# Adafruit_Sparkle_Motion_WLED_Friend.net
KiCad netlist of a schematic drawn in EAGLE
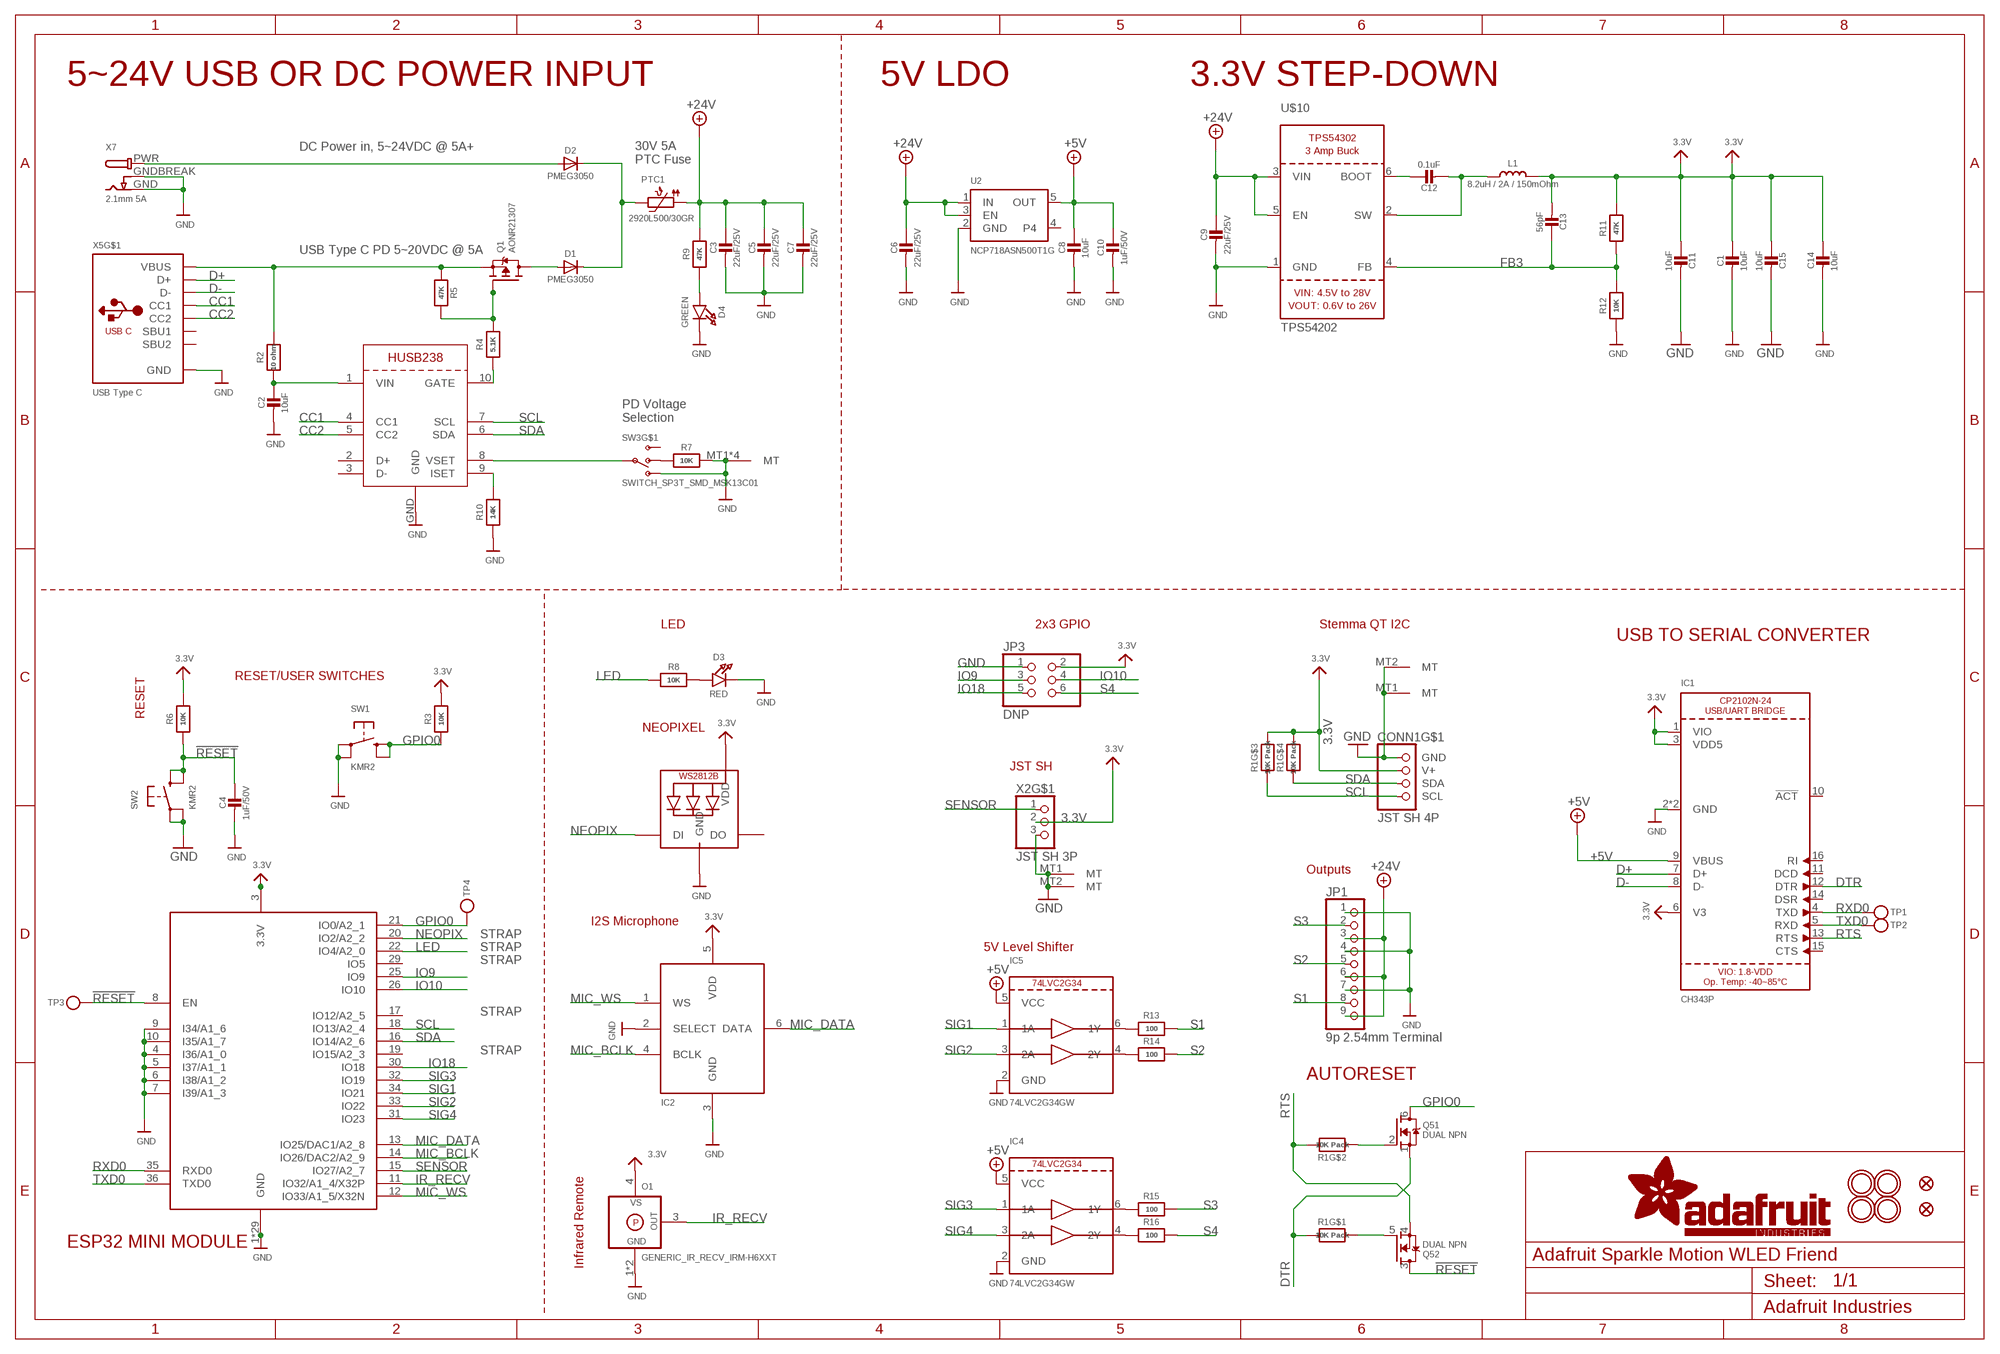
[diagram p0: schematic, sheet 1]

(export (version "E")
  (design (tool "Eeschema 10.0.6"))
  (components
    (comp (ref "C1")
      (value "10uF")
      (footprint "eagle-import:0805-NO")
      (libsource (lib "eagle-import") (part "CAP_CERAMIC0805-NOOUTLINE"))
    )
    (comp (ref "C2")
      (value "10uF")
      (footprint "eagle-import:0805-NO")
      (libsource (lib "eagle-import") (part "CAP_CERAMIC0805-NOOUTLINE"))
    )
    (comp (ref "C3")
      (value "22uF/25V")
      (footprint "eagle-import:0805-NO")
      (libsource (lib "eagle-import") (part "CAP_CERAMIC0805-NOOUTLINE"))
    )
    (comp (ref "C4")
      (value "1uF/50V")
      (footprint "eagle-import:0603-NO")
      (libsource (lib "eagle-import") (part "CAP_CERAMIC0603_NO"))
    )
    (comp (ref "C5")
      (value "22uF/25V")
      (footprint "eagle-import:0805-NO")
      (libsource (lib "eagle-import") (part "CAP_CERAMIC0805-NOOUTLINE"))
    )
    (comp (ref "C6")
      (value "22uF/25V")
      (footprint "eagle-import:0805-NO")
      (libsource (lib "eagle-import") (part "CAP_CERAMIC0805-NOOUTLINE"))
    )
    (comp (ref "C7")
      (value "22uF/25V")
      (footprint "eagle-import:0805-NO")
      (libsource (lib "eagle-import") (part "CAP_CERAMIC0805-NOOUTLINE"))
    )
    (comp (ref "C8")
      (value "10uF")
      (footprint "eagle-import:0805-NO")
      (fields (field (name "REV") "A"))
      (libsource (lib "eagle-import") (part "CAP_CERAMIC0805-NOOUTLINE"))
    )
    (comp (ref "C9")
      (value "22uF/25V")
      (footprint "eagle-import:0805-NO")
      (libsource (lib "eagle-import") (part "CAP_CERAMIC0805-NOOUTLINE"))
    )
    (comp (ref "C10")
      (value "1uF/50V")
      (footprint "eagle-import:0603-NO")
      (libsource (lib "eagle-import") (part "CAP_CERAMIC0603_NO"))
    )
    (comp (ref "C11")
      (value "10uF")
      (footprint "eagle-import:0805-NO")
      (libsource (lib "eagle-import") (part "CAP_CERAMIC0805-NOOUTLINE"))
    )
    (comp (ref "C12")
      (value "0.1uF")
      (footprint "eagle-import:0603-NO")
      (libsource (lib "eagle-import") (part "CAP_CERAMIC0603_NO"))
    )
    (comp (ref "C13")
      (value "56pF")
      (footprint "eagle-import:0603-NO")
      (libsource (lib "eagle-import") (part "CAP_CERAMIC0603_NO"))
    )
    (comp (ref "C14")
      (value "10uF")
      (footprint "eagle-import:0805-NO")
      (libsource (lib "eagle-import") (part "CAP_CERAMIC0805-NOOUTLINE"))
    )
    (comp (ref "C15")
      (value "10uF")
      (footprint "eagle-import:0805-NO")
      (libsource (lib "eagle-import") (part "CAP_CERAMIC0805-NOOUTLINE"))
    )
    (comp (ref "CONN1")
      (value "JST SH 4P")
      (footprint "eagle-import:JST_SH4")
      (libsource (lib "eagle-import") (part "STEMMA_I2C_QT"))
    )
    (comp (ref "D1")
      (value "PMEG3050")
      (footprint "eagle-import:SOD-128")
      (libsource (lib "eagle-import") (part "DIODE_SOD128"))
    )
    (comp (ref "D2")
      (value "PMEG3050")
      (footprint "eagle-import:SOD-128")
      (libsource (lib "eagle-import") (part "DIODE_SOD128"))
    )
    (comp (ref "D3")
      (value "RED")
      (footprint "eagle-import:CHIPLED_0603_NOOUTLINE")
      (libsource (lib "eagle-import") (part "LED0603_NOOUTLINE"))
    )
    (comp (ref "D4")
      (value "GREEN")
      (footprint "eagle-import:CHIPLED_0603_NOOUTLINE")
      (libsource (lib "eagle-import") (part "LED0603_NOOUTLINE"))
    )
    (comp (ref "IC1")
      (value "CH343P")
      (footprint "eagle-import:QFN16_3MM")
      (libsource (lib "eagle-import") (part "CH343P"))
    )
    (comp (ref "IC2")
      (value "ICS-43434")
      (footprint "eagle-import:SPH0645LM4H")
      (libsource (lib "eagle-import") (part "MIC_I2S_SPH0645"))
    )
    (comp (ref "IC4")
      (value "74LVC2G34GW")
      (footprint "eagle-import:SC70-6L")
      (libsource (lib "eagle-import") (part "74LVC2G34GW"))
    )
    (comp (ref "IC5")
      (value "74LVC2G34GW")
      (footprint "eagle-import:SC70-6L")
      (libsource (lib "eagle-import") (part "74LVC2G34GW"))
    )
    (comp (ref "JP1")
      (value "9p 2.54mm Terminal")
      (footprint "eagle-import:1X09_2.54MMTERMINAL")
      (libsource (lib "eagle-import") (part "HEADER-1X9_2.54MMTERM"))
    )
    (comp (ref "JP3")
      (value "DNP")
      (footprint "eagle-import:2X03_ROUND_70MIL")
      (libsource (lib "eagle-import") (part "HEADER-2X3"))
    )
    (comp (ref "L1")
      (value "8.2uH / 2A / 150mOhm")
      (footprint "eagle-import:INDUCTOR_5X5MM_NR5040_NOTHERMALS")
      (libsource (lib "eagle-import") (part "INDUCTORNR5040"))
    )
    (comp (ref "LED1")
      (value "WS2812B_SK6805_1515")
      (footprint "eagle-import:SK6805_1515")
      (libsource (lib "eagle-import") (part "WS2812B_SK6805_1515"))
    )
    (comp (ref "O1")
      (value "GENERIC_IR_RECV_IRM-H6XXT")
      (footprint "eagle-import:IRM-H6XXT")
      (libsource (lib "eagle-import") (part "GENERIC_IR_RECV_IRM-H6XXT"))
    )
    (comp (ref "PTC1")
      (value "2920L500/30GR")
      (footprint "eagle-import:PTC2920")
      (libsource (lib "eagle-import") (part "PTC_2920"))
    )
    (comp (ref "Q1")
      (value "AONR21307")
      (footprint "eagle-import:POWERDI3333")
      (libsource (lib "eagle-import") (part "MOSFET-P-POWERDI3333"))
    )
    (comp (ref "Q5")
      (value "DUAL NPN")
      (footprint "eagle-import:SOT363")
      (fields (field (name "JLC_ROTATION") "0"))
      (libsource (lib "eagle-import") (part "MOSFET-N_DUAL"))
    )
    (comp (ref "R1")
      (value "10K Pack")
      (footprint "eagle-import:RESPACK_4X0603")
      (libsource (lib "eagle-import") (part "RESISTOR_4PACK"))
    )
    (comp (ref "R2")
      (value "10 ohm")
      (footprint "eagle-import:0603-NO")
      (libsource (lib "eagle-import") (part "RESISTOR_0603_NOOUT"))
    )
    (comp (ref "R3")
      (value "10K")
      (footprint "eagle-import:0603-NO")
      (libsource (lib "eagle-import") (part "RESISTOR_0603_NOOUT"))
    )
    (comp (ref "R4")
      (value "5.1K")
      (footprint "eagle-import:0603-NO")
      (libsource (lib "eagle-import") (part "RESISTOR_0603_NOOUT"))
    )
    (comp (ref "R5")
      (value "47K")
      (footprint "eagle-import:0603-NO")
      (libsource (lib "eagle-import") (part "RESISTOR_0603_NOOUT"))
    )
    (comp (ref "R6")
      (value "10K")
      (footprint "eagle-import:0603-NO")
      (libsource (lib "eagle-import") (part "RESISTOR_0603_NOOUT"))
    )
    (comp (ref "R7")
      (value "10K")
      (footprint "eagle-import:0603-NO")
      (libsource (lib "eagle-import") (part "RESISTOR_0603_NOOUT"))
    )
    (comp (ref "R8")
      (value "10K")
      (footprint "eagle-import:0603-NO")
      (libsource (lib "eagle-import") (part "RESISTOR_0603_NOOUT"))
    )
    (comp (ref "R9")
      (value "47K")
      (footprint "eagle-import:0603-NO")
      (libsource (lib "eagle-import") (part "RESISTOR_0603_NOOUT"))
    )
    (comp (ref "R10")
      (value "14K")
      (footprint "eagle-import:0603-NO")
      (libsource (lib "eagle-import") (part "RESISTOR_0603_NOOUT"))
    )
    (comp (ref "R11")
      (value "47K")
      (footprint "eagle-import:0603-NO")
      (libsource (lib "eagle-import") (part "RESISTOR_0603_NOOUT"))
    )
    (comp (ref "R12")
      (value "10K")
      (footprint "eagle-import:0603-NO")
      (libsource (lib "eagle-import") (part "RESISTOR_0603_NOOUT"))
    )
    (comp (ref "R13")
      (value "100")
      (footprint "eagle-import:0603-NO")
      (libsource (lib "eagle-import") (part "RESISTOR_0603_NOOUT"))
    )
    (comp (ref "R14")
      (value "100")
      (footprint "eagle-import:0603-NO")
      (libsource (lib "eagle-import") (part "RESISTOR_0603_NOOUT"))
    )
    (comp (ref "R15")
      (value "100")
      (footprint "eagle-import:0603-NO")
      (libsource (lib "eagle-import") (part "RESISTOR_0603_NOOUT"))
    )
    (comp (ref "R16")
      (value "100")
      (footprint "eagle-import:0603-NO")
      (libsource (lib "eagle-import") (part "RESISTOR_0603_NOOUT"))
    )
    (comp (ref "SW1")
      (value "KMR2")
      (footprint "eagle-import:BTN_RKB2_4.6X2.8")
      (libsource (lib "eagle-import") (part "SWITCH_TACT_SMT_RKB2"))
    )
    (comp (ref "SW2")
      (value "KMR2")
      (footprint "eagle-import:BTN_RKB2_4.6X2.8")
      (libsource (lib "eagle-import") (part "SWITCH_TACT_SMT_RKB2"))
    )
    (comp (ref "SW3")
      (value "SWITCH_SP3T_SMD_MSK13C01")
      (footprint "eagle-import:MSK-13C01")
      (libsource (lib "eagle-import") (part "SWITCH_SP3T_SMD_MSK13C01"))
    )
    (comp (ref "TP1")
      (value "TESTPOINTROUND1.5MM")
      (footprint "eagle-import:TESTPOINT_ROUND_1.5MM")
      (libsource (lib "eagle-import") (part "TESTPOINTROUND1.5MM"))
    )
    (comp (ref "TP2")
      (value "TESTPOINTROUND1.5MM")
      (footprint "eagle-import:TESTPOINT_ROUND_1.5MM")
      (libsource (lib "eagle-import") (part "TESTPOINTROUND1.5MM"))
    )
    (comp (ref "TP3")
      (value "TESTPOINTROUND1.5MM")
      (footprint "eagle-import:TESTPOINT_ROUND_1.5MM")
      (libsource (lib "eagle-import") (part "TESTPOINTROUND1.5MM"))
    )
    (comp (ref "TP4")
      (value "TESTPOINTROUND1.5MM")
      (footprint "eagle-import:TESTPOINT_ROUND_1.5MM")
      (libsource (lib "eagle-import") (part "TESTPOINTROUND1.5MM"))
    )
    (comp (ref "U$10")
      (value "TPS54202")
      (footprint "eagle-import:SOT23-6")
      (libsource (lib "eagle-import") (part "TPS54302"))
    )
    (comp (ref "U$14")
      (value "MOUNTINGHOLE2.5")
      (footprint "eagle-import:MOUNTINGHOLE_2.5_PLATED")
      (libsource (lib "eagle-import") (part "MOUNTINGHOLE2.5"))
    )
    (comp (ref "U$20")
      (value "MOUNTINGHOLE2.5")
      (footprint "eagle-import:MOUNTINGHOLE_2.5_PLATED")
      (libsource (lib "eagle-import") (part "MOUNTINGHOLE2.5"))
    )
    (comp (ref "U$28")
      (value "MOUNTINGHOLE2.5")
      (footprint "eagle-import:MOUNTINGHOLE_2.5_PLATED")
      (libsource (lib "eagle-import") (part "MOUNTINGHOLE2.5"))
    )
    (comp (ref "U$31")
      (value "MOUNTINGHOLE2.5")
      (footprint "eagle-import:MOUNTINGHOLE_2.5_PLATED")
      (libsource (lib "eagle-import") (part "MOUNTINGHOLE2.5"))
    )
    (comp (ref "U$34")
      (value "FIDUCIAL_1MM")
      (footprint "eagle-import:FIDUCIAL_1MM")
      (libsource (lib "eagle-import") (part "FIDUCIAL_1MM"))
    )
    (comp (ref "U$35")
      (value "FIDUCIAL_1MM")
      (footprint "eagle-import:FIDUCIAL_1MM")
      (libsource (lib "eagle-import") (part "FIDUCIAL_1MM"))
    )
    (comp (ref "U2")
      (value "NCP718ASN500T1G")
      (footprint "eagle-import:SOT23-5")
      (fields (field (name "JLC_ROTATION") "0"))
      (libsource (lib "eagle-import") (part "VREG_SOT23-5"))
    )
    (comp (ref "X2")
      (value "JST SH 3P")
      (footprint "eagle-import:JST_SH3")
      (libsource (lib "eagle-import") (part "CON_JST_SH_3PINHORZ"))
    )
    (comp (ref "X3")
      (value "HUSB238")
      (footprint "eagle-import:DFN10_3X3MM")
      (libsource (lib "eagle-import") (part "HUSB238"))
    )
    (comp (ref "X4")
      (value "ESP32-MINI-1")
      (footprint "eagle-import:ESP32-MINI-1")
      (libsource (lib "eagle-import") (part "ESP32-MINI-1"))
    )
    (comp (ref "X5")
      (value "USB Type C")
      (footprint "eagle-import:USB_C_CUSB31-CFM2AX-01-X")
      (libsource (lib "eagle-import") (part "USB_C"))
    )
    (comp (ref "X7")
      (value "2.1mm 5A")
      (footprint "eagle-import:DCJACK_2MM_PTH")
      (libsource (lib "eagle-import") (part "DCBARRELPTH"))
    )
  )
  (nets
    (net (code "1") (name "+5V") (class "Default")
      (node (ref "C10") (pin "1") (pinfunction "1_1") (pintype "passive"))
      (node (ref "C8") (pin "1") (pinfunction "1_1") (pintype "passive"))
      (node (ref "IC1") (pin "9") (pinfunction "VBUS_9") (pintype "power_in"))
      (node (ref "IC4") (pin "5") (pinfunction "VCC_5") (pintype "power_in"))
      (node (ref "IC5") (pin "5") (pinfunction "VCC_5") (pintype "power_in"))
      (node (ref "U2") (pin "5") (pinfunction "OUT_5") (pintype "power_in"))
    )
    (net (code "2") (name "+24V") (class "Default")
      (node (ref "C3") (pin "1") (pinfunction "1_1") (pintype "passive"))
      (node (ref "C5") (pin "1") (pinfunction "1_1") (pintype "passive"))
      (node (ref "C6") (pin "1") (pinfunction "1_1") (pintype "passive"))
      (node (ref "C7") (pin "1") (pinfunction "1_1") (pintype "passive"))
      (node (ref "C9") (pin "1") (pinfunction "1_1") (pintype "passive"))
      (node (ref "JP1") (pin "3") (pinfunction "3_3") (pintype "passive"))
      (node (ref "JP1") (pin "6") (pinfunction "6_6") (pintype "passive"))
      (node (ref "JP1") (pin "9") (pinfunction "9_9") (pintype "passive"))
      (node (ref "PTC1") (pin "P$1") (pinfunction "1_P$1") (pintype "passive"))
      (node (ref "R9") (pin "2") (pinfunction "2_2") (pintype "passive"))
      (node (ref "U$10") (pin "3") (pinfunction "VIN_3") (pintype "power_in"))
      (node (ref "U$10") (pin "5") (pinfunction "EN_5") (pintype "input"))
      (node (ref "U2") (pin "1") (pinfunction "IN_1") (pintype "power_in"))
      (node (ref "U2") (pin "3") (pinfunction "EN_3") (pintype "input"))
    )
    (net (code "3") (name "/CC1") (class "Default")
      (node (ref "X3") (pin "4") (pinfunction "CC1_4") (pintype "input"))
      (node (ref "X5") (pin "A5") (pinfunction "CC1_A5") (pintype "bidirectional"))
    )
    (net (code "4") (name "/CC2") (class "Default")
      (node (ref "X3") (pin "5") (pinfunction "CC2_5") (pintype "input"))
      (node (ref "X5") (pin "B5") (pinfunction "CC2_B5") (pintype "bidirectional"))
    )
    (net (code "5") (name "/D+") (class "Default")
      (node (ref "IC1") (pin "7") (pinfunction "D+_7") (pintype "bidirectional"))
      (node (ref "X5") (pin "A6") (pinfunction "D+_A6") (pintype "bidirectional"))
      (node (ref "X5") (pin "B6") (pinfunction "D+_B6") (pintype "bidirectional"))
    )
    (net (code "6") (name "/D-") (class "Default")
      (node (ref "IC1") (pin "8") (pinfunction "D-_8") (pintype "bidirectional"))
      (node (ref "X5") (pin "A7") (pinfunction "D-_A7") (pintype "bidirectional"))
      (node (ref "X5") (pin "B7") (pinfunction "D-_B7") (pintype "bidirectional"))
    )
    (net (code "7") (name "/DTR") (class "Default")
      (node (ref "IC1") (pin "12") (pinfunction "DTR_12") (pintype "output"))
      (node (ref "Q5") (pin "1") (pinfunction "S_1") (pintype "bidirectional"))
      (node (ref "R1") (pin "1") (pinfunction "1_1") (pintype "passive"))
    )
    (net (code "8") (name "/FB3") (class "Default")
      (node (ref "C13") (pin "1") (pinfunction "1_1") (pintype "passive"))
      (node (ref "R11") (pin "1") (pinfunction "1_1") (pintype "passive"))
      (node (ref "R12") (pin "2") (pinfunction "2_2") (pintype "passive"))
      (node (ref "U$10") (pin "4") (pinfunction "FB_4") (pintype "input"))
    )
    (net (code "9") (name "/GPIO0") (class "Default")
      (node (ref "Q5") (pin "6") (pinfunction "D_6") (pintype "bidirectional"))
      (node (ref "R3") (pin "1") (pinfunction "1_1") (pintype "passive"))
      (node (ref "SW1") (pin "B") (pinfunction "S_B") (pintype "passive"))
      (node (ref "SW1") (pin "B'") (pinfunction "S1_B'") (pintype "passive"))
      (node (ref "TP4") (pin "P$1") (pinfunction "P$1_P$1") (pintype "bidirectional"))
      (node (ref "X4") (pin "21") (pinfunction "IO0/A2_1_21") (pintype "bidirectional"))
    )
    (net (code "10") (name "/IO9") (class "Default")
      (node (ref "JP3") (pin "3") (pinfunction "3_3") (pintype "passive"))
      (node (ref "X4") (pin "25") (pinfunction "IO9_25") (pintype "bidirectional"))
    )
    (net (code "11") (name "/IO10") (class "Default")
      (node (ref "JP3") (pin "4") (pinfunction "4_4") (pintype "passive"))
      (node (ref "X4") (pin "26") (pinfunction "IO10_26") (pintype "bidirectional"))
    )
    (net (code "12") (name "/IO18") (class "Default")
      (node (ref "JP3") (pin "5") (pinfunction "5_5") (pintype "passive"))
      (node (ref "X4") (pin "30") (pinfunction "IO18_30") (pintype "bidirectional"))
    )
    (net (code "13") (name "/IR_RECV") (class "Default")
      (node (ref "O1") (pin "3") (pinfunction "OUT_3") (pintype "output"))
      (node (ref "X4") (pin "11") (pinfunction "IO32/A1_4/X32P_11") (pintype "bidirectional"))
    )
    (net (code "14") (name "/LED") (class "Default")
      (node (ref "R8") (pin "1") (pinfunction "1_1") (pintype "passive"))
      (node (ref "X4") (pin "22") (pinfunction "IO4/A2_0_22") (pintype "bidirectional"))
    )
    (net (code "15") (name "/MIC_BCLK") (class "Default")
      (node (ref "IC2") (pin "4") (pinfunction "BCLK_4") (pintype "input"))
      (node (ref "X4") (pin "14") (pinfunction "IO26/DAC2/A2_9_14") (pintype "bidirectional"))
    )
    (net (code "16") (name "/MIC_DATA") (class "Default")
      (node (ref "IC2") (pin "6") (pinfunction "DATA_6") (pintype "output"))
      (node (ref "X4") (pin "13") (pinfunction "IO25/DAC1/A2_8_13") (pintype "bidirectional"))
    )
    (net (code "17") (name "/MIC_WS") (class "Default")
      (node (ref "IC2") (pin "1") (pinfunction "WS_1") (pintype "input"))
      (node (ref "X4") (pin "12") (pinfunction "IO33/A1_5/X32N_12") (pintype "bidirectional"))
    )
    (net (code "18") (name "/NEOPIX") (class "Default")
      (node (ref "LED1") (pin "1") (pinfunction "DI_1") (pintype "input"))
      (node (ref "X4") (pin "20") (pinfunction "IO2/A2_2_20") (pintype "bidirectional"))
    )
    (net (code "19") (name "/RTS") (class "Default")
      (node (ref "IC1") (pin "13") (pinfunction "RTS_13") (pintype "output"))
      (node (ref "Q5") (pin "4") (pinfunction "S_4") (pintype "bidirectional"))
      (node (ref "R1") (pin "7") (pinfunction "2_7") (pintype "passive"))
    )
    (net (code "20") (name "/RXD0") (class "Default")
      (node (ref "IC1") (pin "4") (pinfunction "TXD_4") (pintype "output"))
      (node (ref "TP1") (pin "P$1") (pinfunction "P$1_P$1") (pintype "bidirectional"))
      (node (ref "X4") (pin "35") (pinfunction "RXD0_35") (pintype "input"))
    )
    (net (code "21") (name "/S1") (class "Default")
      (node (ref "JP1") (pin "8") (pinfunction "8_8") (pintype "passive"))
      (node (ref "R13") (pin "2") (pinfunction "2_2") (pintype "passive"))
    )
    (net (code "22") (name "/S2") (class "Default")
      (node (ref "JP1") (pin "5") (pinfunction "5_5") (pintype "passive"))
      (node (ref "R14") (pin "2") (pinfunction "2_2") (pintype "passive"))
    )
    (net (code "23") (name "/S3") (class "Default")
      (node (ref "JP1") (pin "2") (pinfunction "2_2") (pintype "passive"))
      (node (ref "R15") (pin "2") (pinfunction "2_2") (pintype "passive"))
    )
    (net (code "24") (name "/S4") (class "Default")
      (node (ref "JP3") (pin "6") (pinfunction "6_6") (pintype "passive"))
      (node (ref "R16") (pin "2") (pinfunction "2_2") (pintype "passive"))
    )
    (net (code "25") (name "/SCL") (class "Default")
      (node (ref "CONN1") (pin "4") (pinfunction "SCL_4") (pintype "passive"))
      (node (ref "R1") (pin "3") (pinfunction "1_3") (pintype "passive"))
      (node (ref "X3") (pin "7") (pinfunction "SCL_7") (pintype "bidirectional"))
      (node (ref "X4") (pin "18") (pinfunction "IO13/A2_4_18") (pintype "bidirectional"))
    )
    (net (code "26") (name "/SDA") (class "Default")
      (node (ref "CONN1") (pin "3") (pinfunction "SDA_3") (pintype "passive"))
      (node (ref "R1") (pin "4") (pinfunction "1_4") (pintype "passive"))
      (node (ref "X3") (pin "6") (pinfunction "SDA_6") (pintype "bidirectional"))
      (node (ref "X4") (pin "16") (pinfunction "IO14/A2_6_16") (pintype "bidirectional"))
    )
    (net (code "27") (name "/SENSOR") (class "Default")
      (node (ref "X2") (pin "1") (pinfunction "1_1") (pintype "passive"))
      (node (ref "X4") (pin "15") (pinfunction "IO27/A2_7_15") (pintype "bidirectional"))
    )
    (net (code "28") (name "/SIG1") (class "Default")
      (node (ref "IC5") (pin "1") (pinfunction "1A_1") (pintype "input"))
      (node (ref "X4") (pin "34") (pinfunction "IO21_34") (pintype "bidirectional"))
    )
    (net (code "29") (name "/SIG2") (class "Default")
      (node (ref "IC5") (pin "3") (pinfunction "2A_3") (pintype "input"))
      (node (ref "X4") (pin "33") (pinfunction "IO22_33") (pintype "bidirectional"))
    )
    (net (code "30") (name "/SIG3") (class "Default")
      (node (ref "IC4") (pin "1") (pinfunction "1A_1") (pintype "input"))
      (node (ref "X4") (pin "32") (pinfunction "IO19_32") (pintype "bidirectional"))
    )
    (net (code "31") (name "/SIG4") (class "Default")
      (node (ref "IC4") (pin "3") (pinfunction "2A_3") (pintype "input"))
      (node (ref "X4") (pin "31") (pinfunction "IO23_31") (pintype "bidirectional"))
    )
    (net (code "32") (name "/TXD0") (class "Default")
      (node (ref "IC1") (pin "5") (pinfunction "RXD_5") (pintype "input"))
      (node (ref "TP2") (pin "P$1") (pinfunction "P$1_P$1") (pintype "bidirectional"))
      (node (ref "X4") (pin "36") (pinfunction "TXD0_36") (pintype "output"))
    )
    (net (code "33") (name "/~{RESET}") (class "Default")
      (node (ref "C4") (pin "1") (pinfunction "1_1") (pintype "passive"))
      (node (ref "Q5") (pin "3") (pinfunction "D_3") (pintype "bidirectional"))
      (node (ref "R6") (pin "1") (pinfunction "1_1") (pintype "passive"))
      (node (ref "SW2") (pin "B") (pinfunction "S_B") (pintype "passive"))
      (node (ref "SW2") (pin "B'") (pinfunction "S1_B'") (pintype "passive"))
      (node (ref "TP3") (pin "P$1") (pinfunction "P$1_P$1") (pintype "bidirectional"))
      (node (ref "X4") (pin "8") (pinfunction "EN_8") (pintype "input"))
    )
    (net (code "34") (name "3.3V") (class "Default")
      (node (ref "C1") (pin "1") (pinfunction "1_1") (pintype "passive"))
      (node (ref "C11") (pin "1") (pinfunction "1_1") (pintype "passive"))
      (node (ref "C13") (pin "2") (pinfunction "2_2") (pintype "passive"))
      (node (ref "C14") (pin "1") (pinfunction "1_1") (pintype "passive"))
      (node (ref "C15") (pin "1") (pinfunction "1_1") (pintype "passive"))
      (node (ref "CONN1") (pin "2") (pinfunction "V+_2") (pintype "passive"))
      (node (ref "IC1") (pin "1") (pinfunction "VIO_1") (pintype "power_in"))
      (node (ref "IC1") (pin "3") (pinfunction "VDD5_3") (pintype "power_in"))
      (node (ref "IC1") (pin "6") (pinfunction "V3_6") (pintype "passive"))
      (node (ref "IC2") (pin "5") (pinfunction "VDD_5") (pintype "power_in"))
      (node (ref "JP3") (pin "2") (pinfunction "2_2") (pintype "passive"))
      (node (ref "L1") (pin "P$2") (pinfunction "2_P$2") (pintype "passive"))
      (node (ref "LED1") (pin "2") (pinfunction "VDD_2") (pintype "power_in"))
      (node (ref "O1") (pin "4") (pinfunction "VS_4") (pintype "power_in"))
      (node (ref "R1") (pin "5") (pinfunction "2_5") (pintype "passive"))
      (node (ref "R1") (pin "6") (pinfunction "2_6") (pintype "passive"))
      (node (ref "R11") (pin "2") (pinfunction "2_2") (pintype "passive"))
      (node (ref "R3") (pin "2") (pinfunction "2_2") (pintype "passive"))
      (node (ref "R6") (pin "2") (pinfunction "2_2") (pintype "passive"))
      (node (ref "X2") (pin "2") (pinfunction "2_2") (pintype "passive"))
      (node (ref "X4") (pin "3") (pinfunction "3.3V_3") (pintype "passive"))
    )
    (net (code "35") (name "GND") (class "Default")
      (node (ref "C1") (pin "2") (pinfunction "2_2") (pintype "passive"))
      (node (ref "C10") (pin "2") (pinfunction "2_2") (pintype "passive"))
      (node (ref "C11") (pin "2") (pinfunction "2_2") (pintype "passive"))
      (node (ref "C14") (pin "2") (pinfunction "2_2") (pintype "passive"))
      (node (ref "C15") (pin "2") (pinfunction "2_2") (pintype "passive"))
      (node (ref "C2") (pin "2") (pinfunction "2_2") (pintype "passive"))
      (node (ref "C3") (pin "2") (pinfunction "2_2") (pintype "passive"))
      (node (ref "C4") (pin "2") (pinfunction "2_2") (pintype "passive"))
      (node (ref "C5") (pin "2") (pinfunction "2_2") (pintype "passive"))
      (node (ref "C6") (pin "2") (pinfunction "2_2") (pintype "passive"))
      (node (ref "C7") (pin "2") (pinfunction "2_2") (pintype "passive"))
      (node (ref "C8") (pin "2") (pinfunction "2_2") (pintype "passive"))
      (node (ref "C9") (pin "2") (pinfunction "2_2") (pintype "passive"))
      (node (ref "CONN1") (pin "1") (pinfunction "GND_1") (pintype "passive"))
      (node (ref "CONN1") (pin "MT1") (pinfunction "MT_MT1") (pintype "bidirectional"))
      (node (ref "CONN1") (pin "MT2") (pinfunction "MT_MT2") (pintype "bidirectional"))
      (node (ref "D3") (pin "C") (pinfunction "C_C") (pintype "passive"))
      (node (ref "D4") (pin "C") (pinfunction "C_C") (pintype "passive"))
      (node (ref "IC1") (pin "2") (pinfunction "GND_2") (pintype "power_in"))
      (node (ref "IC1") (pin "THERMAL") (pinfunction "GND_THERMAL") (pintype "power_in"))
      (node (ref "IC2") (pin "2") (pinfunction "SELECT_2") (pintype "input"))
      (node (ref "IC2") (pin "3") (pinfunction "GND_3") (pintype "power_in"))
      (node (ref "IC4") (pin "2") (pinfunction "GND_2") (pintype "power_in"))
      (node (ref "IC5") (pin "2") (pinfunction "GND_2") (pintype "power_in"))
      (node (ref "JP1") (pin "1") (pinfunction "1_1") (pintype "passive"))
      (node (ref "JP1") (pin "4") (pinfunction "4_4") (pintype "passive"))
      (node (ref "JP1") (pin "7") (pinfunction "7_7") (pintype "passive"))
      (node (ref "JP3") (pin "1") (pinfunction "1_1") (pintype "passive"))
      (node (ref "LED1") (pin "4") (pinfunction "GND_4") (pintype "power_in"))
      (node (ref "O1") (pin "1") (pinfunction "GND_1") (pintype "power_in"))
      (node (ref "O1") (pin "2") (pinfunction "GND_2") (pintype "power_in"))
      (node (ref "R10") (pin "1") (pinfunction "1_1") (pintype "passive"))
      (node (ref "R12") (pin "1") (pinfunction "1_1") (pintype "passive"))
      (node (ref "R7") (pin "1") (pinfunction "1_1") (pintype "passive"))
      (node (ref "SW1") (pin "A") (pinfunction "P_A") (pintype "passive"))
      (node (ref "SW1") (pin "A'") (pinfunction "P1_A'") (pintype "passive"))
      (node (ref "SW2") (pin "A") (pinfunction "P_A") (pintype "passive"))
      (node (ref "SW2") (pin "A'") (pinfunction "P1_A'") (pintype "passive"))
      (node (ref "SW3") (pin "4") (pinfunction "3_4") (pintype "passive"))
      (node (ref "SW3") (pin "MT1") (pinfunction "MT_MT1") (pintype "bidirectional"))
      (node (ref "SW3") (pin "MT2") (pinfunction "MT_MT2") (pintype "bidirectional"))
      (node (ref "SW3") (pin "MT3") (pinfunction "MT_MT3") (pintype "bidirectional"))
      (node (ref "SW3") (pin "MT4") (pinfunction "MT_MT4") (pintype "bidirectional"))
      (node (ref "U$10") (pin "1") (pinfunction "GND_1") (pintype "power_in"))
      (node (ref "U2") (pin "2") (pinfunction "GND_2") (pintype "power_in"))
      (node (ref "X2") (pin "3") (pinfunction "3_3") (pintype "passive"))
      (node (ref "X2") (pin "MT1") (pinfunction "MT_MT1") (pintype "bidirectional"))
      (node (ref "X2") (pin "MT2") (pinfunction "MT_MT2") (pintype "bidirectional"))
      (node (ref "X3") (pin "GND") (pinfunction "GND_GND") (pintype "power_in"))
      (node (ref "X4") (pin "1") (pinfunction "GND_1") (pintype "passive"))
      (node (ref "X4") (pin "10") (pinfunction "I35/A1_7_10") (pintype "input"))
      (node (ref "X4") (pin "2") (pinfunction "GND_2") (pintype "passive"))
      (node (ref "X4") (pin "27") (pinfunction "GND_27") (pintype "passive"))
      (node (ref "X4") (pin "38") (pinfunction "GND_38") (pintype "passive"))
      (node (ref "X4") (pin "39") (pinfunction "GND_39") (pintype "passive"))
      (node (ref "X4") (pin "4") (pinfunction "I36/A1_0_4") (pintype "input"))
      (node (ref "X4") (pin "40") (pinfunction "GND_40") (pintype "passive"))
      (node (ref "X4") (pin "41") (pinfunction "GND_41") (pintype "passive"))
      (node (ref "X4") (pin "42") (pinfunction "GND_42") (pintype "passive"))
      (node (ref "X4") (pin "43") (pinfunction "GND_43") (pintype "passive"))
      (node (ref "X4") (pin "44") (pinfunction "GND_44") (pintype "passive"))
      (node (ref "X4") (pin "45") (pinfunction "GND_45") (pintype "passive"))
      (node (ref "X4") (pin "46") (pinfunction "GND_46") (pintype "passive"))
      (node (ref "X4") (pin "47") (pinfunction "GND_47") (pintype "passive"))
      (node (ref "X4") (pin "48") (pinfunction "GND_48") (pintype "passive"))
      (node (ref "X4") (pin "49") (pinfunction "GND_49") (pintype "passive"))
      (node (ref "X4") (pin "5") (pinfunction "I37/A1_1_5") (pintype "input"))
      (node (ref "X4") (pin "50") (pinfunction "GND_50") (pintype "passive"))
      (node (ref "X4") (pin "51") (pinfunction "GND_51") (pintype "passive"))
      (node (ref "X4") (pin "52") (pinfunction "GND_52") (pintype "passive"))
      (node (ref "X4") (pin "53") (pinfunction "GND_53") (pintype "passive"))
      (node (ref "X4") (pin "54") (pinfunction "GND_54") (pintype "passive"))
      (node (ref "X4") (pin "55") (pinfunction "GND_55") (pintype "passive"))
      (node (ref "X4") (pin "56") (pinfunction "GND_56") (pintype "passive"))
      (node (ref "X4") (pin "57") (pinfunction "GND_57") (pintype "passive"))
      (node (ref "X4") (pin "58") (pinfunction "GND_58") (pintype "passive"))
      (node (ref "X4") (pin "59") (pinfunction "GND_59") (pintype "passive"))
      (node (ref "X4") (pin "6") (pinfunction "I38/A1_2_6") (pintype "input"))
      (node (ref "X4") (pin "60") (pinfunction "GND_60") (pintype "passive"))
      (node (ref "X4") (pin "61") (pinfunction "GND_61") (pintype "passive"))
      (node (ref "X4") (pin "62") (pinfunction "GND_62") (pintype "passive"))
      (node (ref "X4") (pin "63") (pinfunction "GND_63") (pintype "passive"))
      (node (ref "X4") (pin "7") (pinfunction "I39/A1_3_7") (pintype "input"))
      (node (ref "X4") (pin "9") (pinfunction "I34/A1_6_9") (pintype "input"))
      (node (ref "X5") (pin "A1B12") (pinfunction "GND_A1B12") (pintype "power_in"))
      (node (ref "X5") (pin "B1A12") (pinfunction "GND_B1A12") (pintype "power_in"))
      (node (ref "X7") (pin "GND") (pinfunction "GND_GND") (pintype "power_in"))
      (node (ref "X7") (pin "GNDBREAK") (pinfunction "GNDBREAK_GNDBREAK") (pintype "power_in"))
    )
    (net (code "36") (name "Net-(D2-PadA)") (class "Default")
      (node (ref "D2") (pin "A") (pinfunction "A_A") (pintype "passive"))
      (node (ref "X7") (pin "PWR") (pinfunction "PWR_PWR") (pintype "power_in"))
    )
    (net (code "37") (name "Net-(D3-PadA)") (class "Default")
      (node (ref "D3") (pin "A") (pinfunction "A_A") (pintype "passive"))
      (node (ref "R8") (pin "2") (pinfunction "2_2") (pintype "passive"))
    )
    (net (code "38") (name "Net-(D4-PadA)") (class "Default")
      (node (ref "D4") (pin "A") (pinfunction "A_A") (pintype "passive"))
      (node (ref "R9") (pin "1") (pinfunction "1_1") (pintype "passive"))
    )
    (net (code "39") (name "Net-(IC4-1Y)") (class "Default")
      (node (ref "IC4") (pin "6") (pinfunction "1Y_6") (pintype "output"))
      (node (ref "R15") (pin "1") (pinfunction "1_1") (pintype "passive"))
    )
    (net (code "40") (name "Net-(IC4-2Y)") (class "Default")
      (node (ref "IC4") (pin "4") (pinfunction "2Y_4") (pintype "output"))
      (node (ref "R16") (pin "1") (pinfunction "1_1") (pintype "passive"))
    )
    (net (code "41") (name "Net-(IC5-1Y)") (class "Default")
      (node (ref "IC5") (pin "6") (pinfunction "1Y_6") (pintype "output"))
      (node (ref "R13") (pin "1") (pinfunction "1_1") (pintype "passive"))
    )
    (net (code "42") (name "Net-(IC5-2Y)") (class "Default")
      (node (ref "IC5") (pin "4") (pinfunction "2Y_4") (pintype "output"))
      (node (ref "R14") (pin "1") (pinfunction "1_1") (pintype "passive"))
    )
    (net (code "43") (name "Net-(L1-1)") (class "Default")
      (node (ref "C12") (pin "2") (pinfunction "2_2") (pintype "passive"))
      (node (ref "L1") (pin "P$1") (pinfunction "1_P$1") (pintype "passive"))
      (node (ref "U$10") (pin "2") (pinfunction "SW_2") (pintype "power_in"))
    )
    (net (code "44") (name "Net-(PTC1-2)") (class "Default")
      (node (ref "D1") (pin "C") (pinfunction "C_C") (pintype "passive"))
      (node (ref "D2") (pin "C") (pinfunction "C_C") (pintype "passive"))
      (node (ref "PTC1") (pin "P$2") (pinfunction "2_P$2") (pintype "passive"))
    )
    (net (code "45") (name "Net-(Q1-D)") (class "Default")
      (node (ref "D1") (pin "A") (pinfunction "A_A") (pintype "passive"))
      (node (ref "Q1") (pin "5678") (pinfunction "D_5678") (pintype "passive"))
    )
    (net (code "46") (name "Net-(Q1-G)") (class "Default")
      (node (ref "Q1") (pin "4") (pinfunction "G_4") (pintype "passive"))
      (node (ref "R4") (pin "2") (pinfunction "2_2") (pintype "passive"))
      (node (ref "R5") (pin "2") (pinfunction "2_2") (pintype "passive"))
    )
    (net (code "47") (name "Net-(Q1-S-Pad1)") (class "Default")
      (node (ref "Q1") (pin "1") (pinfunction "S_1") (pintype "passive"))
      (node (ref "Q1") (pin "2") (pinfunction "S_2") (pintype "passive"))
      (node (ref "Q1") (pin "3") (pinfunction "S_3") (pintype "passive"))
      (node (ref "R2") (pin "2") (pinfunction "2_2") (pintype "passive"))
      (node (ref "R5") (pin "1") (pinfunction "1_1") (pintype "passive"))
      (node (ref "X5") (pin "A4B9") (pinfunction "VBUS_A4B9") (pintype "power_in"))
      (node (ref "X5") (pin "B4A9") (pinfunction "VBUS_B4A9") (pintype "power_in"))
    )
    (net (code "48") (name "Net-(Q5A-G)") (class "Default")
      (node (ref "Q5") (pin "2") (pinfunction "G_2") (pintype "bidirectional"))
      (node (ref "R1") (pin "2") (pinfunction "1_2") (pintype "passive"))
    )
    (net (code "49") (name "Net-(Q5B-G)") (class "Default")
      (node (ref "Q5") (pin "5") (pinfunction "G_5") (pintype "bidirectional"))
      (node (ref "R1") (pin "8") (pinfunction "2_8") (pintype "passive"))
    )
    (net (code "50") (name "Net-(R7-Pad2)") (class "Default")
      (node (ref "R7") (pin "2") (pinfunction "2_2") (pintype "passive"))
      (node (ref "SW3") (pin "2") (pinfunction "2_2") (pintype "passive"))
    )
    (net (code "51") (name "Net-(SW3A-P)") (class "Default")
      (node (ref "SW3") (pin "3") (pinfunction "P_3") (pintype "passive"))
      (node (ref "X3") (pin "8") (pinfunction "VSET_8") (pintype "passive"))
    )
    (net (code "52") (name "Net-(U$10-BOOT)") (class "Default")
      (node (ref "C12") (pin "1") (pinfunction "1_1") (pintype "passive"))
      (node (ref "U$10") (pin "6") (pinfunction "BOOT_6") (pintype "passive"))
    )
    (net (code "53") (name "Net-(X3-GATE)") (class "Default")
      (node (ref "R4") (pin "1") (pinfunction "1_1") (pintype "passive"))
      (node (ref "X3") (pin "10") (pinfunction "GATE_10") (pintype "output"))
    )
    (net (code "54") (name "Net-(X3-ISET)") (class "Default")
      (node (ref "R10") (pin "2") (pinfunction "2_2") (pintype "passive"))
      (node (ref "X3") (pin "9") (pinfunction "ISET_9") (pintype "passive"))
    )
    (net (code "55") (name "Net-(X3-VIN)") (class "Default")
      (node (ref "C2") (pin "1") (pinfunction "1_1") (pintype "passive"))
      (node (ref "R2") (pin "1") (pinfunction "1_1") (pintype "passive"))
      (node (ref "X3") (pin "1") (pinfunction "VIN_1") (pintype "power_in"))
    )
    (net (code "56") (name "unconnected-(IC1-CTS-Pad15)") (class "Default")
      (node (ref "IC1") (pin "15") (pinfunction "CTS_15") (pintype "input"))
    )
    (net (code "57") (name "unconnected-(IC1-DCD-Pad11)") (class "Default")
      (node (ref "IC1") (pin "11") (pinfunction "DCD_11") (pintype "input"))
    )
    (net (code "58") (name "unconnected-(IC1-DSR-Pad14)") (class "Default")
      (node (ref "IC1") (pin "14") (pinfunction "DSR_14") (pintype "input"))
    )
    (net (code "59") (name "unconnected-(IC1-RI-Pad16)") (class "Default")
      (node (ref "IC1") (pin "16") (pinfunction "RI_16") (pintype "input"))
    )
    (net (code "60") (name "unconnected-(IC1-~{ACT}-Pad10)") (class "Default")
      (node (ref "IC1") (pin "10") (pinfunction "~{ACT}_10") (pintype "bidirectional"))
    )
    (net (code "61") (name "unconnected-(LED1-DO-Pad3)") (class "Default")
      (node (ref "LED1") (pin "3") (pinfunction "DO_3") (pintype "output"))
    )
    (net (code "62") (name "unconnected-(SW3-Pad1)") (class "Default")
      (node (ref "SW3") (pin "1") (pinfunction "1_1") (pintype "passive"))
    )
    (net (code "63") (name "unconnected-(U2-P4-Pad4)") (class "Default")
      (node (ref "U2") (pin "4") (pinfunction "P4_4") (pintype "bidirectional"))
    )
    (net (code "64") (name "unconnected-(X3-D+-Pad2)") (class "Default")
      (node (ref "X3") (pin "2") (pinfunction "D+_2") (pintype "input"))
    )
    (net (code "65") (name "unconnected-(X3-D--Pad3)") (class "Default")
      (node (ref "X3") (pin "3") (pinfunction "D-_3") (pintype "input"))
    )
    (net (code "66") (name "unconnected-(X4-IO5-Pad29)") (class "Default")
      (node (ref "X4") (pin "29") (pinfunction "IO5_29") (pintype "bidirectional"))
    )
    (net (code "67") (name "unconnected-(X4-IO12{slash}A2_5-Pad17)") (class "Default")
      (node (ref "X4") (pin "17") (pinfunction "IO12/A2_5_17") (pintype "bidirectional"))
    )
    (net (code "68") (name "unconnected-(X4-IO15{slash}A2_3-Pad19)") (class "Default")
      (node (ref "X4") (pin "19") (pinfunction "IO15/A2_3_19") (pintype "bidirectional"))
    )
    (net (code "69") (name "unconnected-(X5A-SBU1-PadA8)") (class "Default")
      (node (ref "X5") (pin "A8") (pinfunction "SBU1_A8") (pintype "bidirectional"))
    )
    (net (code "70") (name "unconnected-(X5A-SBU2-PadB8)") (class "Default")
      (node (ref "X5") (pin "B8") (pinfunction "SBU2_B8") (pintype "bidirectional"))
    )
  )
)
